# SB2232_v01.net
KiCad netlist of a schematic drawn in Altium Designer
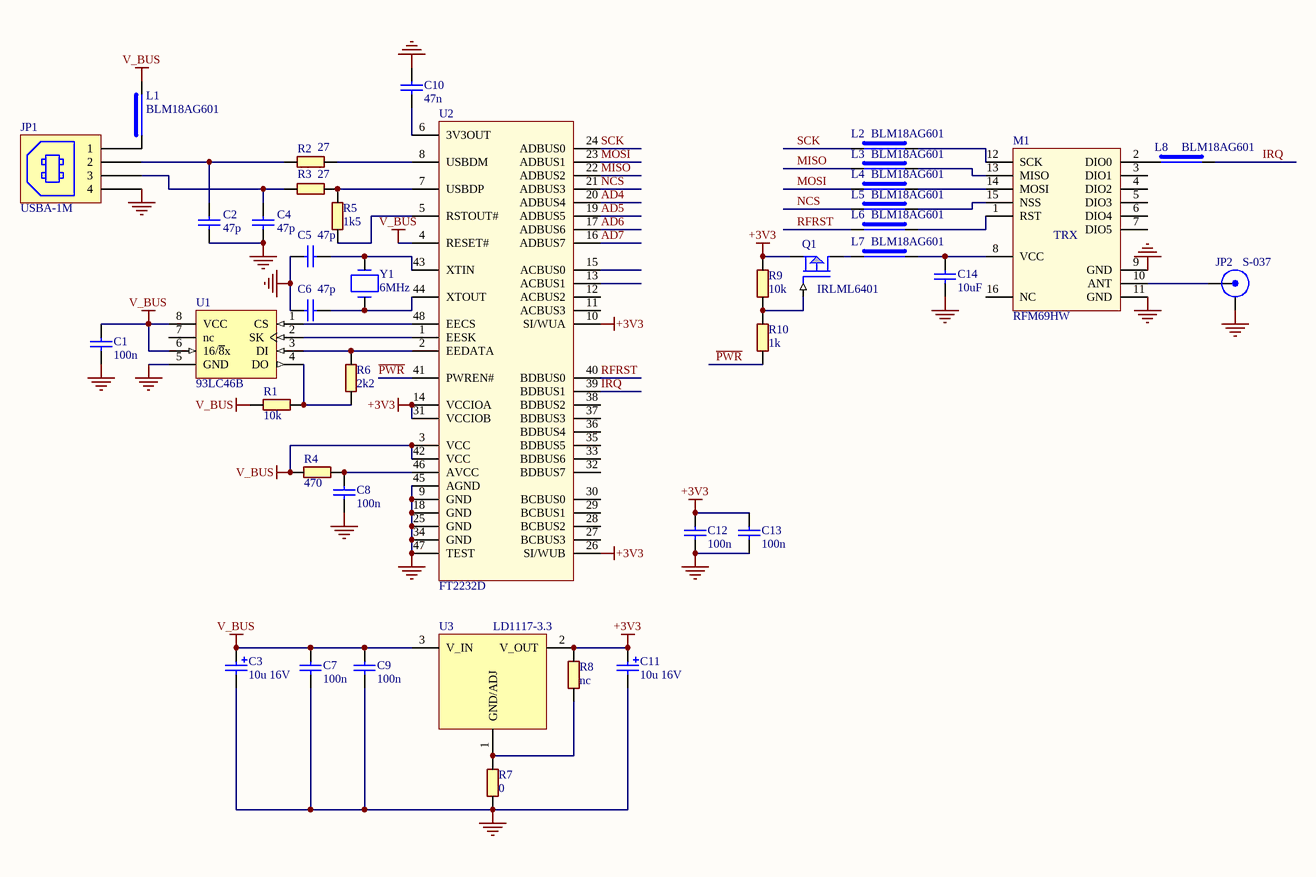
[diagram p0: SB2232_v01.SchDoc]

(export (version "E")
  (design (tool "Eeschema 10.0.6"))
  (components
    (comp (ref "C1") (value "100n") (footprint "CAPC1608X08N") (libsource (lib "Discrete") (part "CAPN")))
    (comp (ref "C2") (value "47p") (footprint "CAPC1608X08N") (libsource (lib "Discrete") (part "CAPN")))
    (comp (ref "C3") (value "10u 16V") (footprint "CAPMP3217X18N") (libsource (lib "Discrete") (part "CAPP")))
    (comp (ref "C4") (value "47p") (footprint "CAPC1608X08N") (libsource (lib "Discrete") (part "CAPN")))
    (comp (ref "C5") (value "47p") (footprint "CAPC1608X08N") (libsource (lib "Discrete") (part "CAPN")))
    (comp (ref "C6") (value "47p") (footprint "CAPC1608X08N") (libsource (lib "Discrete") (part "CAPN")))
    (comp (ref "C7") (value "100n") (footprint "CAPC1608X08N") (libsource (lib "Discrete") (part "CAPN")))
    (comp (ref "C8") (value "100n") (footprint "CAPC1608X08N") (libsource (lib "Discrete") (part "CAPN")))
    (comp (ref "C9") (value "100n") (footprint "CAPC1608X08N") (libsource (lib "Discrete") (part "CAPN")))
    (comp (ref "C10") (value "47n") (footprint "CAPC1608X08N") (libsource (lib "Discrete") (part "CAPN")))
    (comp (ref "C11")
      (value "10u 16V")
      (footprint "CAPMP3217X18N")
      (libsource (lib "Discrete") (part "CAPP"))
    )
    (comp (ref "C12") (value "100n") (footprint "CAPC1608X08N") (libsource (lib "Discrete") (part "CAPN")))
    (comp (ref "C13") (value "100n") (footprint "CAPC1608X08N") (libsource (lib "Discrete") (part "CAPN")))
    (comp (ref "C14") (value "10uF") (footprint "CAPC2012X11N") (libsource (lib "Discrete") (part "CAPN")))
    (comp (ref "JP1")
      (value "USBA-1M")
      (footprint "USB_A_M_SMD")
      (description "USB_connector")
      (libsource (lib "jlink072") (part "USB_conn"))
    )
    (comp (ref "JP2")
      (value "S-037")
      (footprint "S-037_3D")
      (description "RF Connector")
      (libsource (lib "RFM_PS_V01") (part "BNC"))
    )
    (comp (ref "L1")
      (value "BLM18AG601")
      (footprint "INDC1608X10N")
      (libsource (lib "RFM_PS_V01") (part "SUPRESOR"))
    )
    (comp (ref "L2")
      (value "BLM18AG601")
      (footprint "INDC1608X10N")
      (libsource (lib "RFM_PS_V01") (part "SUPRESOR"))
    )
    (comp (ref "L3")
      (value "BLM18AG601")
      (footprint "INDC1608X10N")
      (libsource (lib "RFM_PS_V01") (part "SUPRESOR"))
    )
    (comp (ref "L4")
      (value "BLM18AG601")
      (footprint "INDC1608X10N")
      (libsource (lib "RFM_PS_V01") (part "SUPRESOR"))
    )
    (comp (ref "L5")
      (value "BLM18AG601")
      (footprint "INDC1608X10N")
      (libsource (lib "RFM_PS_V01") (part "SUPRESOR"))
    )
    (comp (ref "L6")
      (value "BLM18AG601")
      (footprint "INDC1608X10N")
      (libsource (lib "RFM_PS_V01") (part "SUPRESOR"))
    )
    (comp (ref "L7")
      (value "BLM18AG601")
      (footprint "INDC1608X10N")
      (libsource (lib "RFM_PS_V01") (part "SUPRESOR"))
    )
    (comp (ref "L8")
      (value "BLM18AG601")
      (footprint "INDC1608X10N")
      (libsource (lib "RFM_PS_V01") (part "SUPRESOR"))
    )
    (comp (ref "M1")
      (value "RFM69HW")
      (footprint "LGA16_RFM69")
      (libsource (lib "CLAP_M505_WL_BP_V22") (part "RFM69HW_V13_2"))
    )
    (comp (ref "Q1")
      (value "IRLML6401")
      (footprint "SOT-23")
      (libsource (lib "CLAP_M505_WL_BP_V22") (part "MOSF-P"))
    )
    (comp (ref "R1") (value "10k") (footprint "RESC1608X06N") (libsource (lib "") (part "RES_2")))
    (comp (ref "R2") (value "27") (footprint "RESC1608X06N") (libsource (lib "") (part "RES_1")))
    (comp (ref "R3") (value "27") (footprint "RESC1608X06N") (libsource (lib "") (part "RES_1")))
    (comp (ref "R4") (value "470") (footprint "RESC1608X06N") (libsource (lib "") (part "RES_1")))
    (comp (ref "R5") (value "1k5") (footprint "RESC1608X06N") (libsource (lib "Discrete") (part "RES")))
    (comp (ref "R6") (value "2k2") (footprint "RESC1608X06N") (libsource (lib "Discrete") (part "RES")))
    (comp (ref "R7") (value "0") (footprint "RESC1608X06N") (libsource (lib "Discrete") (part "RES")))
    (comp (ref "R8") (value "nc") (footprint "RESC1608X06N") (libsource (lib "Discrete") (part "RES")))
    (comp (ref "R9") (value "10k") (footprint "RESC1608X06N") (libsource (lib "Discrete") (part "RES")))
    (comp (ref "R10") (value "1k") (footprint "RESC1608X06N") (libsource (lib "Discrete") (part "RES")))
    (comp (ref "U1")
      (value "93LC46B")
      (footprint "SOIC127P600X175-8N")
      (description "3-wire EEPROM")
      (libsource (lib "ICs") (part "93C56"))
    )
    (comp (ref "U2")
      (value "FT2232D")
      (footprint "TSQFP50P900X900X160-48N")
      (libsource (lib "SB") (part "FT2232D"))
    )
    (comp (ref "U3")
      (value "LD1117-3.3")
      (footprint "SOT230P700X180-4N")
      (libsource (lib "RFM_PS_V01") (part "LM1117_3.3"))
    )
    (comp (ref "Y1")
      (value "6MHz")
      (footprint "XTAL_HC49P488W45L1117T490H350")
      (libsource (lib "Discrete") (part "Y"))
    )
  )
  (nets
    (net (code "1") (name "+3V3") (class "Default")
      (node (ref "C11") (pin "2") (pinfunction "2_2") (pintype "passive"))
      (node (ref "C12") (pin "1") (pinfunction "1_1") (pintype "passive"))
      (node (ref "C13") (pin "1") (pinfunction "1_1") (pintype "passive"))
      (node (ref "Q1") (pin "3") (pinfunction "SOURCE_3") (pintype "passive"))
      (node (ref "R8") (pin "2") (pinfunction "2_2") (pintype "passive"))
      (node (ref "R9") (pin "2") (pinfunction "2_2") (pintype "passive"))
      (node (ref "U2") (pin "10") (pinfunction "SI/WUA_10") (pintype "passive"))
      (node (ref "U2") (pin "14") (pinfunction "VCCIOA_14") (pintype "passive"))
      (node (ref "U2") (pin "26") (pinfunction "SI/WUB_26") (pintype "passive"))
      (node (ref "U2") (pin "31") (pinfunction "VCCIOB_31") (pintype "passive"))
      (node (ref "U3") (pin "2") (pinfunction "V_OUT_2") (pintype "passive"))
    )
    (net (code "2") (name "/AD4") (class "Default")
      (node (ref "U2") (pin "20") (pinfunction "ADBUS4_20") (pintype "passive"))
    )
    (net (code "3") (name "/AD5") (class "Default")
      (node (ref "U2") (pin "19") (pinfunction "ADBUS5_19") (pintype "passive"))
    )
    (net (code "4") (name "/AD6") (class "Default")
      (node (ref "U2") (pin "17") (pinfunction "ADBUS6_17") (pintype "passive"))
    )
    (net (code "5") (name "/AD7") (class "Default")
      (node (ref "U2") (pin "16") (pinfunction "ADBUS7_16") (pintype "passive"))
    )
    (net (code "6") (name "/IRQ") (class "Default")
      (node (ref "L8") (pin "2") (pinfunction "2_2") (pintype "passive"))
      (node (ref "U2") (pin "39") (pinfunction "BDBUS1_39") (pintype "passive"))
    )
    (net (code "7") (name "/MISO") (class "Default")
      (node (ref "L3") (pin "1") (pinfunction "1_1") (pintype "passive"))
      (node (ref "U2") (pin "22") (pinfunction "ADBUS2_22") (pintype "passive"))
    )
    (net (code "8") (name "/MOSI") (class "Default")
      (node (ref "L4") (pin "1") (pinfunction "1_1") (pintype "passive"))
      (node (ref "U2") (pin "23") (pinfunction "ADBUS1_23") (pintype "passive"))
    )
    (net (code "9") (name "/NCS") (class "Default")
      (node (ref "L5") (pin "1") (pinfunction "1_1") (pintype "passive"))
      (node (ref "U2") (pin "21") (pinfunction "ADBUS3_21") (pintype "passive"))
    )
    (net (code "10") (name "/RFRST") (class "Default")
      (node (ref "L6") (pin "1") (pinfunction "1_1") (pintype "passive"))
      (node (ref "U2") (pin "40") (pinfunction "BDBUS0_40") (pintype "passive"))
    )
    (net (code "11") (name "/SCK") (class "Default")
      (node (ref "L2") (pin "1") (pinfunction "1_1") (pintype "passive"))
      (node (ref "U2") (pin "24") (pinfunction "ADBUS0_24") (pintype "passive"))
    )
    (net (code "12") (name "/~{PWR}") (class "Default")
      (node (ref "R10") (pin "1") (pinfunction "1_1") (pintype "passive"))
      (node (ref "U2") (pin "41") (pinfunction "PWREN#_41") (pintype "passive"))
    )
    (net (code "13") (name "GND") (class "Default")
      (node (ref "C1") (pin "2") (pinfunction "2_2") (pintype "passive"))
      (node (ref "C10") (pin "1") (pinfunction "1_1") (pintype "passive"))
      (node (ref "C11") (pin "1") (pinfunction "1_1") (pintype "passive"))
      (node (ref "C12") (pin "2") (pinfunction "2_2") (pintype "passive"))
      (node (ref "C13") (pin "2") (pinfunction "2_2") (pintype "passive"))
      (node (ref "C14") (pin "2") (pinfunction "2_2") (pintype "passive"))
      (node (ref "C2") (pin "2") (pinfunction "2_2") (pintype "passive"))
      (node (ref "C3") (pin "1") (pinfunction "1_1") (pintype "passive"))
      (node (ref "C4") (pin "2") (pinfunction "2_2") (pintype "passive"))
      (node (ref "C5") (pin "1") (pinfunction "1_1") (pintype "passive"))
      (node (ref "C6") (pin "1") (pinfunction "1_1") (pintype "passive"))
      (node (ref "C7") (pin "2") (pinfunction "2_2") (pintype "passive"))
      (node (ref "C8") (pin "2") (pinfunction "2_2") (pintype "passive"))
      (node (ref "C9") (pin "2") (pinfunction "2_2") (pintype "passive"))
      (node (ref "JP1") (pin "4") (pinfunction "4_4") (pintype "passive"))
      (node (ref "JP2") (pin "2") (pinfunction "Y_2") (pintype "passive"))
      (node (ref "M1") (pin "11") (pinfunction "GND_11") (pintype "passive"))
      (node (ref "M1") (pin "9") (pinfunction "GND_9") (pintype "passive"))
      (node (ref "R7") (pin "1") (pinfunction "1_1") (pintype "passive"))
      (node (ref "U1") (pin "5") (pinfunction "GND_5") (pintype "power_in"))
      (node (ref "U2") (pin "18") (pinfunction "GND_18") (pintype "passive"))
      (node (ref "U2") (pin "25") (pinfunction "GND_25") (pintype "passive"))
      (node (ref "U2") (pin "34") (pinfunction "GND_34") (pintype "passive"))
      (node (ref "U2") (pin "45") (pinfunction "AGND_45") (pintype "passive"))
      (node (ref "U2") (pin "47") (pinfunction "TEST_47") (pintype "passive"))
      (node (ref "U2") (pin "9") (pinfunction "GND_9") (pintype "passive"))
    )
    (net (code "14") (name "Net-(C2-Pad1)") (class "Default")
      (node (ref "C2") (pin "1") (pinfunction "1_1") (pintype "passive"))
      (node (ref "JP1") (pin "2") (pinfunction "2_2") (pintype "passive"))
      (node (ref "R2") (pin "1") (pinfunction "1_1") (pintype "passive"))
    )
    (net (code "15") (name "Net-(C4-Pad1)") (class "Default")
      (node (ref "C4") (pin "1") (pinfunction "1_1") (pintype "passive"))
      (node (ref "JP1") (pin "3") (pinfunction "3_3") (pintype "passive"))
      (node (ref "R3") (pin "1") (pinfunction "1_1") (pintype "passive"))
    )
    (net (code "16") (name "Net-(JP1-Pad1)") (class "Default")
      (node (ref "JP1") (pin "1") (pinfunction "1_1") (pintype "passive"))
      (node (ref "L1") (pin "1") (pinfunction "1_1") (pintype "passive"))
    )
    (net (code "17") (name "Net-(JP2-X)") (class "Default")
      (node (ref "JP2") (pin "1") (pinfunction "X_1") (pintype "passive"))
      (node (ref "M1") (pin "10") (pinfunction "ANT_10") (pintype "passive"))
    )
    (net (code "18") (name "Net-(M1-DIO0)") (class "Default")
      (node (ref "L8") (pin "1") (pinfunction "1_1") (pintype "passive"))
      (node (ref "M1") (pin "2") (pinfunction "DIO0_2") (pintype "passive"))
    )
    (net (code "19") (name "Net-(M1-MISO)") (class "Default")
      (node (ref "L3") (pin "2") (pinfunction "2_2") (pintype "passive"))
      (node (ref "M1") (pin "13") (pinfunction "MISO_13") (pintype "passive"))
    )
    (net (code "20") (name "Net-(M1-MOSI)") (class "Default")
      (node (ref "L4") (pin "2") (pinfunction "2_2") (pintype "passive"))
      (node (ref "M1") (pin "14") (pinfunction "MOSI_14") (pintype "passive"))
    )
    (net (code "21") (name "Net-(M1-NSS)") (class "Default")
      (node (ref "L5") (pin "2") (pinfunction "2_2") (pintype "passive"))
      (node (ref "M1") (pin "15") (pinfunction "NSS_15") (pintype "passive"))
    )
    (net (code "22") (name "Net-(M1-RST)") (class "Default")
      (node (ref "L6") (pin "2") (pinfunction "2_2") (pintype "passive"))
      (node (ref "M1") (pin "1") (pinfunction "RST_1") (pintype "passive"))
    )
    (net (code "23") (name "Net-(M1-SCK)") (class "Default")
      (node (ref "L2") (pin "2") (pinfunction "2_2") (pintype "passive"))
      (node (ref "M1") (pin "12") (pinfunction "SCK_12") (pintype "passive"))
    )
    (net (code "24") (name "Net-(M1-VCC)") (class "Default")
      (node (ref "C14") (pin "1") (pinfunction "1_1") (pintype "passive"))
      (node (ref "L7") (pin "2") (pinfunction "2_2") (pintype "passive"))
      (node (ref "M1") (pin "8") (pinfunction "VCC_8") (pintype "passive"))
    )
    (net (code "25") (name "Net-(Q1-DRAIN)") (class "Default")
      (node (ref "L7") (pin "1") (pinfunction "1_1") (pintype "passive"))
      (node (ref "Q1") (pin "2") (pinfunction "DRAIN_2") (pintype "passive"))
    )
    (net (code "26") (name "Net-(Q1-GATE)") (class "Default")
      (node (ref "Q1") (pin "1") (pinfunction "GATE_1") (pintype "input"))
      (node (ref "R10") (pin "2") (pinfunction "2_2") (pintype "passive"))
      (node (ref "R9") (pin "1") (pinfunction "1_1") (pintype "passive"))
    )
    (net (code "27") (name "Net-(U1-CS)") (class "Default")
      (node (ref "U1") (pin "1") (pinfunction "CS_1") (pintype "input"))
      (node (ref "U2") (pin "48") (pinfunction "EECS_48") (pintype "passive"))
    )
    (net (code "28") (name "Net-(U1-DI)") (class "Default")
      (node (ref "R6") (pin "2") (pinfunction "2_2") (pintype "passive"))
      (node (ref "U1") (pin "3") (pinfunction "DI_3") (pintype "input"))
      (node (ref "U2") (pin "2") (pinfunction "EEDATA_2") (pintype "passive"))
    )
    (net (code "29") (name "Net-(U1-DO)") (class "Default")
      (node (ref "R1") (pin "1") (pinfunction "1_1") (pintype "passive"))
      (node (ref "R6") (pin "1") (pinfunction "1_1") (pintype "passive"))
      (node (ref "U1") (pin "4") (pinfunction "DO_4") (pintype "output"))
    )
    (net (code "30") (name "Net-(U1-SK)") (class "Default")
      (node (ref "U1") (pin "2") (pinfunction "SK_2") (pintype "input"))
      (node (ref "U2") (pin "1") (pinfunction "EESK_1") (pintype "passive"))
    )
    (net (code "31") (name "Net-(U2-3V3OUT)") (class "Default")
      (node (ref "C10") (pin "2") (pinfunction "2_2") (pintype "passive"))
      (node (ref "U2") (pin "6") (pinfunction "3V3OUT_6") (pintype "passive"))
    )
    (net (code "32") (name "Net-(U2-AVCC)") (class "Default")
      (node (ref "C8") (pin "1") (pinfunction "1_1") (pintype "passive"))
      (node (ref "R4") (pin "2") (pinfunction "2_2") (pintype "passive"))
      (node (ref "U2") (pin "46") (pinfunction "AVCC_46") (pintype "passive"))
    )
    (net (code "33") (name "Net-(U2-RSTOUT#)") (class "Default")
      (node (ref "R5") (pin "1") (pinfunction "1_1") (pintype "passive"))
      (node (ref "U2") (pin "5") (pinfunction "RSTOUT#_5") (pintype "passive"))
    )
    (net (code "34") (name "Net-(U2-USBDM)") (class "Default")
      (node (ref "R2") (pin "2") (pinfunction "2_2") (pintype "passive"))
      (node (ref "U2") (pin "8") (pinfunction "USBDM_8") (pintype "passive"))
    )
    (net (code "35") (name "Net-(U2-USBDP)") (class "Default")
      (node (ref "R3") (pin "2") (pinfunction "2_2") (pintype "passive"))
      (node (ref "R5") (pin "2") (pinfunction "2_2") (pintype "passive"))
      (node (ref "U2") (pin "7") (pinfunction "USBDP_7") (pintype "passive"))
    )
    (net (code "36") (name "Net-(U2-XTIN)") (class "Default")
      (node (ref "C5") (pin "2") (pinfunction "2_2") (pintype "passive"))
      (node (ref "U2") (pin "43") (pinfunction "XTIN_43") (pintype "passive"))
      (node (ref "Y1") (pin "2") (pinfunction "2_2") (pintype "passive"))
    )
    (net (code "37") (name "Net-(U2-XTOUT)") (class "Default")
      (node (ref "C6") (pin "2") (pinfunction "2_2") (pintype "passive"))
      (node (ref "U2") (pin "44") (pinfunction "XTOUT_44") (pintype "passive"))
      (node (ref "Y1") (pin "1") (pinfunction "1_1") (pintype "passive"))
    )
    (net (code "38") (name "Net-(U3-GND{slash}ADJ)") (class "Default")
      (node (ref "R7") (pin "2") (pinfunction "2_2") (pintype "passive"))
      (node (ref "R8") (pin "1") (pinfunction "1_1") (pintype "passive"))
      (node (ref "U3") (pin "1") (pinfunction "GND/ADJ_1") (pintype "passive"))
    )
    (net (code "39") (name "V_BUS") (class "Default")
      (node (ref "C1") (pin "1") (pinfunction "1_1") (pintype "passive"))
      (node (ref "C3") (pin "2") (pinfunction "2_2") (pintype "passive"))
      (node (ref "C7") (pin "1") (pinfunction "1_1") (pintype "passive"))
      (node (ref "C9") (pin "1") (pinfunction "1_1") (pintype "passive"))
      (node (ref "L1") (pin "2") (pinfunction "2_2") (pintype "passive"))
      (node (ref "R1") (pin "2") (pinfunction "2_2") (pintype "passive"))
      (node (ref "R4") (pin "1") (pinfunction "1_1") (pintype "passive"))
      (node (ref "U1") (pin "6") (pinfunction "16/~{8}x_6") (pintype "input"))
      (node (ref "U1") (pin "8") (pinfunction "VCC_8") (pintype "power_in"))
      (node (ref "U2") (pin "3") (pinfunction "VCC_3") (pintype "passive"))
      (node (ref "U2") (pin "4") (pinfunction "RESET#_4") (pintype "passive"))
      (node (ref "U2") (pin "42") (pinfunction "VCC_42") (pintype "passive"))
      (node (ref "U3") (pin "3") (pinfunction "V_IN_3") (pintype "passive"))
    )
    (net (code "40") (name "unconnected-(M1-DIO1-Pad3)") (class "Default")
      (node (ref "M1") (pin "3") (pinfunction "DIO1_3") (pintype "passive"))
    )
    (net (code "41") (name "unconnected-(M1-DIO2-Pad4)") (class "Default")
      (node (ref "M1") (pin "4") (pinfunction "DIO2_4") (pintype "passive"))
    )
    (net (code "42") (name "unconnected-(M1-DIO3-Pad5)") (class "Default")
      (node (ref "M1") (pin "5") (pinfunction "DIO3_5") (pintype "passive"))
    )
    (net (code "43") (name "unconnected-(M1-DIO4-Pad6)") (class "Default")
      (node (ref "M1") (pin "6") (pinfunction "DIO4_6") (pintype "passive"))
    )
    (net (code "44") (name "unconnected-(M1-DIO5-Pad7)") (class "Default")
      (node (ref "M1") (pin "7") (pinfunction "DIO5_7") (pintype "passive"))
    )
    (net (code "45") (name "unconnected-(M1-NC-Pad16)") (class "Default")
      (node (ref "M1") (pin "16") (pinfunction "NC_16") (pintype "passive"))
    )
    (net (code "46") (name "unconnected-(U1-nc-Pad7)") (class "Default")
      (node (ref "U1") (pin "7") (pinfunction "nc_7") (pintype "passive"))
    )
    (net (code "47") (name "unconnected-(U2-ACBUS0-Pad15)") (class "Default")
      (node (ref "U2") (pin "15") (pinfunction "ACBUS0_15") (pintype "passive"))
    )
    (net (code "48") (name "unconnected-(U2-ACBUS1-Pad13)") (class "Default")
      (node (ref "U2") (pin "13") (pinfunction "ACBUS1_13") (pintype "passive"))
    )
    (net (code "49") (name "unconnected-(U2-ACBUS2-Pad12)") (class "Default")
      (node (ref "U2") (pin "12") (pinfunction "ACBUS2_12") (pintype "passive"))
    )
    (net (code "50") (name "unconnected-(U2-ACBUS3-Pad11)") (class "Default")
      (node (ref "U2") (pin "11") (pinfunction "ACBUS3_11") (pintype "passive"))
    )
    (net (code "51") (name "unconnected-(U2-BCBUS0-Pad30)") (class "Default")
      (node (ref "U2") (pin "30") (pinfunction "BCBUS0_30") (pintype "passive"))
    )
    (net (code "52") (name "unconnected-(U2-BCBUS1-Pad29)") (class "Default")
      (node (ref "U2") (pin "29") (pinfunction "BCBUS1_29") (pintype "passive"))
    )
    (net (code "53") (name "unconnected-(U2-BCBUS2-Pad28)") (class "Default")
      (node (ref "U2") (pin "28") (pinfunction "BCBUS2_28") (pintype "passive"))
    )
    (net (code "54") (name "unconnected-(U2-BCBUS3-Pad27)") (class "Default")
      (node (ref "U2") (pin "27") (pinfunction "BCBUS3_27") (pintype "passive"))
    )
    (net (code "55") (name "unconnected-(U2-BDBUS2-Pad38)") (class "Default")
      (node (ref "U2") (pin "38") (pinfunction "BDBUS2_38") (pintype "passive"))
    )
    (net (code "56") (name "unconnected-(U2-BDBUS3-Pad37)") (class "Default")
      (node (ref "U2") (pin "37") (pinfunction "BDBUS3_37") (pintype "passive"))
    )
    (net (code "57") (name "unconnected-(U2-BDBUS4-Pad36)") (class "Default")
      (node (ref "U2") (pin "36") (pinfunction "BDBUS4_36") (pintype "passive"))
    )
    (net (code "58") (name "unconnected-(U2-BDBUS5-Pad35)") (class "Default")
      (node (ref "U2") (pin "35") (pinfunction "BDBUS5_35") (pintype "passive"))
    )
    (net (code "59") (name "unconnected-(U2-BDBUS6-Pad33)") (class "Default")
      (node (ref "U2") (pin "33") (pinfunction "BDBUS6_33") (pintype "passive"))
    )
    (net (code "60") (name "unconnected-(U2-BDBUS7-Pad32)") (class "Default")
      (node (ref "U2") (pin "32") (pinfunction "BDBUS7_32") (pintype "passive"))
    )
  )
)
